# tlc5940.net
KiCad netlist of a schematic drawn in EAGLE
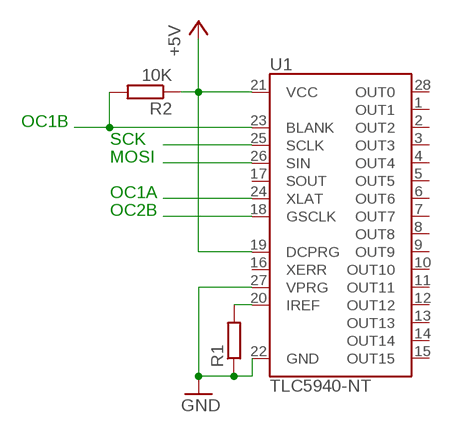
[diagram p0: schematic, sheet 1]

(export (version "E")
  (design (tool "Eeschema 10.0.6"))
  (components
    (comp (ref "R1")
      (value "R-EU_0207/10")
      (footprint "eagle-import:0207_10")
      (libsource (lib "eagle-import") (part "R-EU_0207/10"))
    )
    (comp (ref "R2")
      (value "10K")
      (footprint "eagle-import:0207_10")
      (libsource (lib "eagle-import") (part "R-EU_0207/10"))
    )
    (comp (ref "U1")
      (value "TLC5940-NT")
      (footprint "eagle-import:DIL28-3")
      (libsource (lib "eagle-import") (part "TLC5940-NT"))
    )
  )
  (nets
    (net (code "1") (name "+5V") (class "Default")
      (node (ref "R2") (pin "1") (pinfunction "1_1") (pintype "passive"))
      (node (ref "U1") (pin "19") (pinfunction "DCPRG_19") (pintype "bidirectional"))
      (node (ref "U1") (pin "21") (pinfunction "VCC_21") (pintype "bidirectional"))
    )
    (net (code "2") (name "GND") (class "Default")
      (node (ref "R1") (pin "1") (pinfunction "1_1") (pintype "passive"))
      (node (ref "U1") (pin "22") (pinfunction "GND_22") (pintype "bidirectional"))
      (node (ref "U1") (pin "27") (pinfunction "VPRG_27") (pintype "bidirectional"))
    )
    (net (code "3") (name "Net-(U1-BLANK)") (class "Default")
      (node (ref "R2") (pin "2") (pinfunction "2_2") (pintype "passive"))
      (node (ref "U1") (pin "23") (pinfunction "BLANK_23") (pintype "bidirectional"))
    )
    (net (code "4") (name "Net-(U1-IREF)") (class "Default")
      (node (ref "R1") (pin "2") (pinfunction "2_2") (pintype "passive"))
      (node (ref "U1") (pin "20") (pinfunction "IREF_20") (pintype "bidirectional"))
    )
    (net (code "5") (name "unconnected-(U1-GSCLK-Pad18)") (class "Default")
      (node (ref "U1") (pin "18") (pinfunction "GSCLK_18") (pintype "bidirectional"))
    )
    (net (code "6") (name "unconnected-(U1-OUT0-Pad28)") (class "Default")
      (node (ref "U1") (pin "28") (pinfunction "OUT0_28") (pintype "bidirectional"))
    )
    (net (code "7") (name "unconnected-(U1-OUT1-Pad1)") (class "Default")
      (node (ref "U1") (pin "1") (pinfunction "OUT1_1") (pintype "bidirectional"))
    )
    (net (code "8") (name "unconnected-(U1-OUT2-Pad2)") (class "Default")
      (node (ref "U1") (pin "2") (pinfunction "OUT2_2") (pintype "bidirectional"))
    )
    (net (code "9") (name "unconnected-(U1-OUT3-Pad3)") (class "Default")
      (node (ref "U1") (pin "3") (pinfunction "OUT3_3") (pintype "bidirectional"))
    )
    (net (code "10") (name "unconnected-(U1-OUT4-Pad4)") (class "Default")
      (node (ref "U1") (pin "4") (pinfunction "OUT4_4") (pintype "bidirectional"))
    )
    (net (code "11") (name "unconnected-(U1-OUT5-Pad5)") (class "Default")
      (node (ref "U1") (pin "5") (pinfunction "OUT5_5") (pintype "bidirectional"))
    )
    (net (code "12") (name "unconnected-(U1-OUT6-Pad6)") (class "Default")
      (node (ref "U1") (pin "6") (pinfunction "OUT6_6") (pintype "bidirectional"))
    )
    (net (code "13") (name "unconnected-(U1-OUT7-Pad7)") (class "Default")
      (node (ref "U1") (pin "7") (pinfunction "OUT7_7") (pintype "bidirectional"))
    )
    (net (code "14") (name "unconnected-(U1-OUT8-Pad8)") (class "Default")
      (node (ref "U1") (pin "8") (pinfunction "OUT8_8") (pintype "bidirectional"))
    )
    (net (code "15") (name "unconnected-(U1-OUT9-Pad9)") (class "Default")
      (node (ref "U1") (pin "9") (pinfunction "OUT9_9") (pintype "bidirectional"))
    )
    (net (code "16") (name "unconnected-(U1-OUT10-Pad10)") (class "Default")
      (node (ref "U1") (pin "10") (pinfunction "OUT10_10") (pintype "bidirectional"))
    )
    (net (code "17") (name "unconnected-(U1-OUT11-Pad11)") (class "Default")
      (node (ref "U1") (pin "11") (pinfunction "OUT11_11") (pintype "bidirectional"))
    )
    (net (code "18") (name "unconnected-(U1-OUT12-Pad12)") (class "Default")
      (node (ref "U1") (pin "12") (pinfunction "OUT12_12") (pintype "bidirectional"))
    )
    (net (code "19") (name "unconnected-(U1-OUT13-Pad13)") (class "Default")
      (node (ref "U1") (pin "13") (pinfunction "OUT13_13") (pintype "bidirectional"))
    )
    (net (code "20") (name "unconnected-(U1-OUT14-Pad14)") (class "Default")
      (node (ref "U1") (pin "14") (pinfunction "OUT14_14") (pintype "bidirectional"))
    )
    (net (code "21") (name "unconnected-(U1-OUT15-Pad15)") (class "Default")
      (node (ref "U1") (pin "15") (pinfunction "OUT15_15") (pintype "bidirectional"))
    )
    (net (code "22") (name "unconnected-(U1-SCLK-Pad25)") (class "Default")
      (node (ref "U1") (pin "25") (pinfunction "SCLK_25") (pintype "bidirectional"))
    )
    (net (code "23") (name "unconnected-(U1-SIN-Pad26)") (class "Default")
      (node (ref "U1") (pin "26") (pinfunction "SIN_26") (pintype "bidirectional"))
    )
    (net (code "24") (name "unconnected-(U1-SOUT-Pad17)") (class "Default")
      (node (ref "U1") (pin "17") (pinfunction "SOUT_17") (pintype "bidirectional"))
    )
    (net (code "25") (name "unconnected-(U1-XERR-Pad16)") (class "Default")
      (node (ref "U1") (pin "16") (pinfunction "XERR_16") (pintype "bidirectional"))
    )
    (net (code "26") (name "unconnected-(U1-XLAT-Pad24)") (class "Default")
      (node (ref "U1") (pin "24") (pinfunction "XLAT_24") (pintype "bidirectional"))
    )
  )
)
